# SOS-Water-Ingress-Sensor.net
KiCad netlist of a schematic drawn in EAGLE
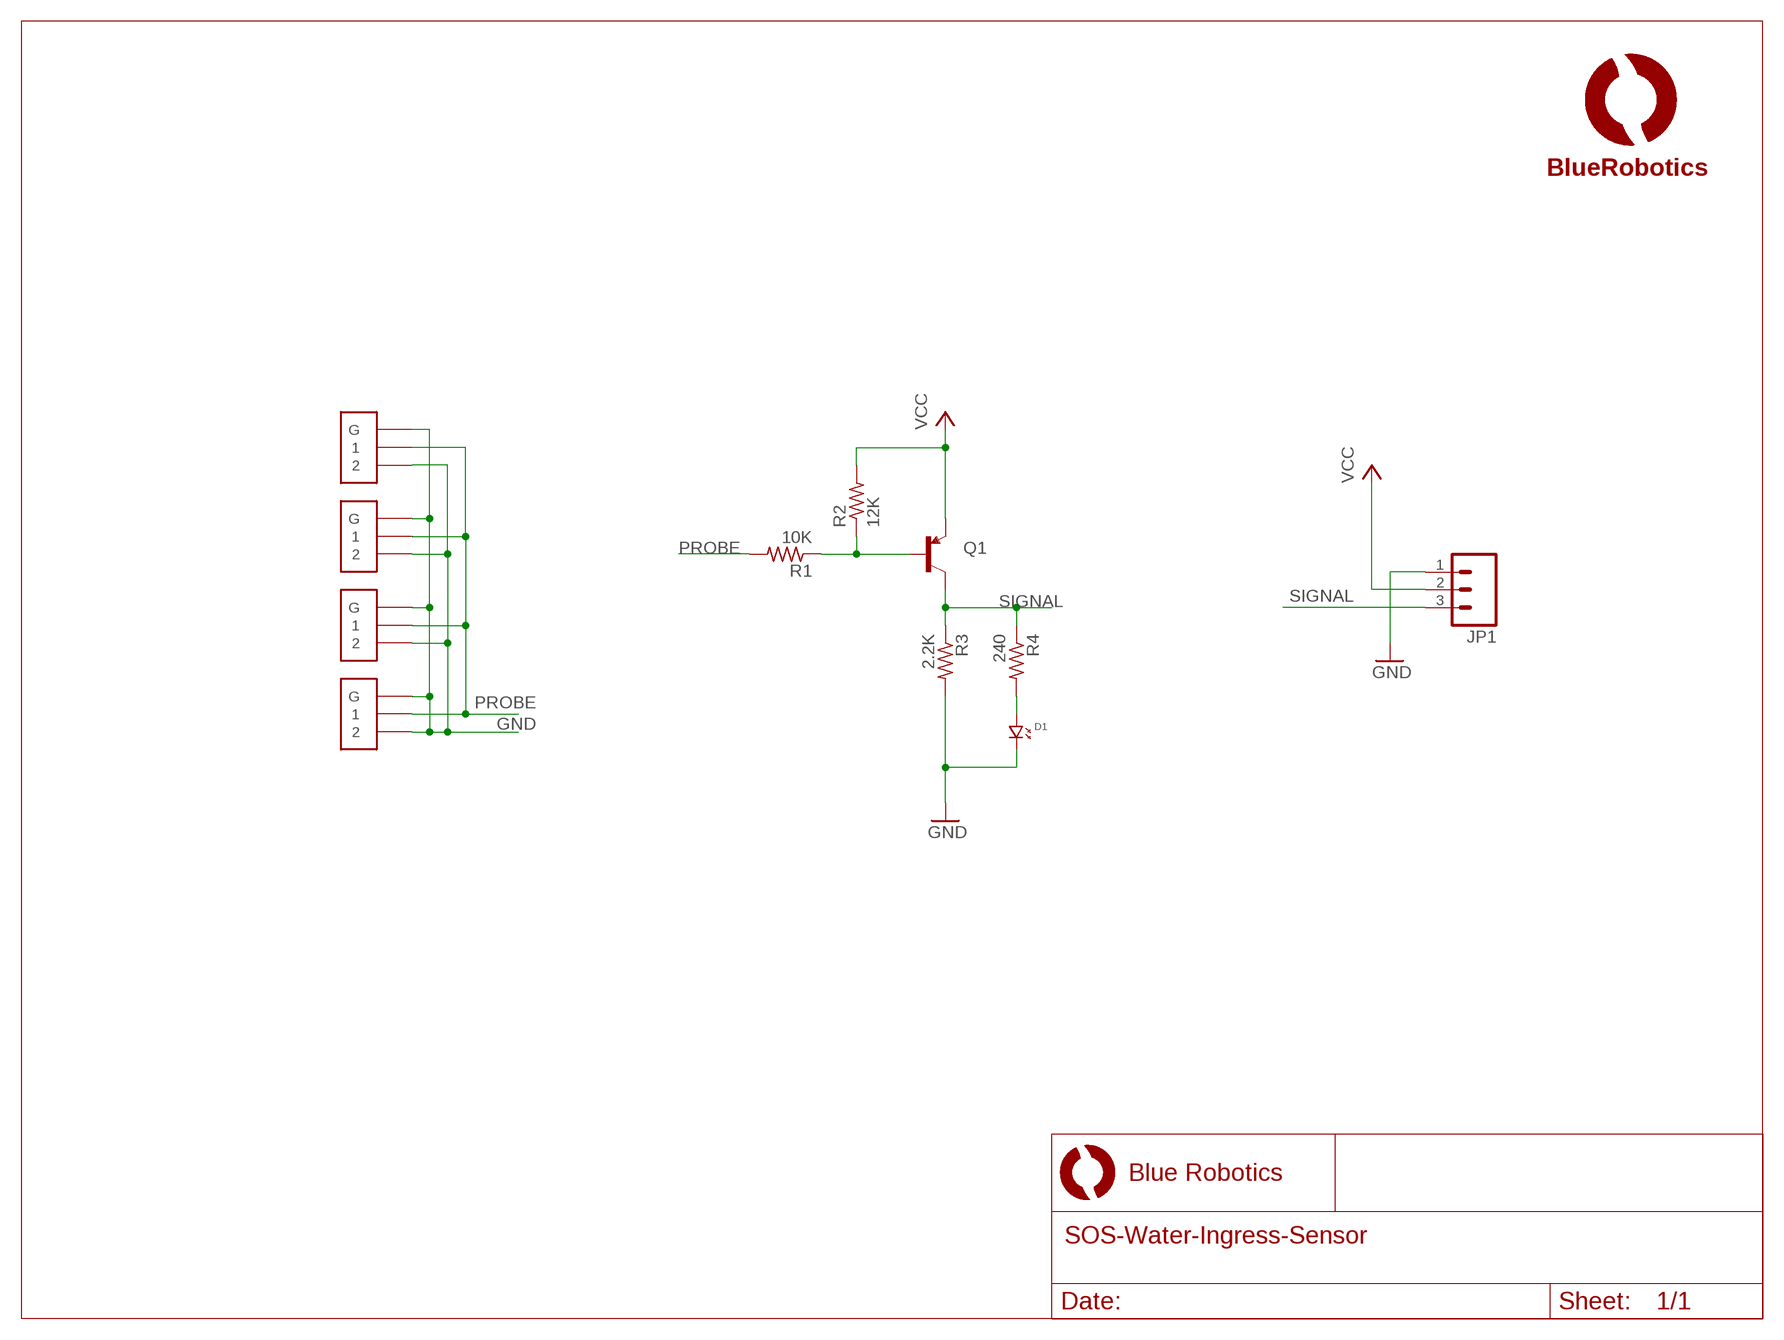
[diagram p0: schematic, sheet 1]

(export (version "E")
  (design (tool "Eeschema 10.0.6"))
  (components
    (comp (ref "D1")
      (value "LED.0805")
      (footprint "eagle-import:0805.LED")
      (libsource (lib "eagle-import") (part "LED.0805"))
    )
    (comp (ref "JP1")
      (value "M03PTH")
      (footprint "eagle-import:1X03")
      (libsource (lib "eagle-import") (part "M03PTH"))
    )
    (comp (ref "Q1")
      (value "TRANSISTOR_PNPSMD")
      (footprint "eagle-import:SOT23-3")
      (libsource (lib "eagle-import") (part "TRANSISTOR_PNPSMD"))
    )
    (comp (ref "R1")
      (value "10K")
      (footprint "eagle-import:R0603")
      (libsource (lib "eagle-import") (part "R-US_R0603"))
    )
    (comp (ref "R2")
      (value "12K")
      (footprint "eagle-import:R0603")
      (libsource (lib "eagle-import") (part "R-US_R0603"))
    )
    (comp (ref "R3")
      (value "2.2K")
      (footprint "eagle-import:R0603")
      (libsource (lib "eagle-import") (part "R-US_R0603"))
    )
    (comp (ref "R4")
      (value "240")
      (footprint "eagle-import:R0603")
      (libsource (lib "eagle-import") (part "R-US_R0603"))
    )
    (comp (ref "U$1")
      (value "JSH-GH-2VERT")
      (footprint "eagle-import:JST-GH-TOP-2")
      (libsource (lib "eagle-import") (part "JSH-GH-2VERT"))
    )
    (comp (ref "U$2")
      (value "JSH-GH-2VERT")
      (footprint "eagle-import:JST-GH-TOP-2")
      (libsource (lib "eagle-import") (part "JSH-GH-2VERT"))
    )
    (comp (ref "U$3")
      (value "JSH-GH-2VERT")
      (footprint "eagle-import:JST-GH-TOP-2")
      (libsource (lib "eagle-import") (part "JSH-GH-2VERT"))
    )
    (comp (ref "U$4")
      (value "JSH-GH-2VERT")
      (footprint "eagle-import:JST-GH-TOP-2")
      (libsource (lib "eagle-import") (part "JSH-GH-2VERT"))
    )
    (comp (ref "U$7")
      (value "LOGOBR-LOGO-S")
      (footprint "eagle-import:BR-LOGO-SMALL")
      (libsource (lib "eagle-import") (part "LOGOBR-LOGO-S"))
    )
  )
  (nets
    (net (code "1") (name "/PROBE") (class "Default")
      (node (ref "R1") (pin "2") (pinfunction "2_2") (pintype "passive"))
      (node (ref "U$1") (pin "1") (pinfunction "1_1") (pintype "bidirectional"))
      (node (ref "U$2") (pin "1") (pinfunction "1_1") (pintype "bidirectional"))
      (node (ref "U$3") (pin "1") (pinfunction "1_1") (pintype "bidirectional"))
      (node (ref "U$4") (pin "1") (pinfunction "1_1") (pintype "bidirectional"))
    )
    (net (code "2") (name "/SIGNAL") (class "Default")
      (node (ref "JP1") (pin "3") (pinfunction "3_3") (pintype "passive"))
      (node (ref "Q1") (pin "3") (pinfunction "C_3") (pintype "passive"))
      (node (ref "R3") (pin "1") (pinfunction "1_1") (pintype "passive"))
      (node (ref "R4") (pin "1") (pinfunction "1_1") (pintype "passive"))
    )
    (net (code "3") (name "GND") (class "Default")
      (node (ref "D1") (pin "P$2") (pinfunction "2_P$2") (pintype "bidirectional"))
      (node (ref "JP1") (pin "1") (pinfunction "1_1") (pintype "passive"))
      (node (ref "R3") (pin "2") (pinfunction "2_2") (pintype "passive"))
      (node (ref "U$1") (pin "2") (pinfunction "2_2") (pintype "bidirectional"))
      (node (ref "U$1") (pin "MECH1") (pinfunction "G_MECH1") (pintype "bidirectional"))
      (node (ref "U$1") (pin "MECH2") (pinfunction "G_MECH2") (pintype "bidirectional"))
      (node (ref "U$2") (pin "2") (pinfunction "2_2") (pintype "bidirectional"))
      (node (ref "U$2") (pin "MECH1") (pinfunction "G_MECH1") (pintype "bidirectional"))
      (node (ref "U$2") (pin "MECH2") (pinfunction "G_MECH2") (pintype "bidirectional"))
      (node (ref "U$3") (pin "2") (pinfunction "2_2") (pintype "bidirectional"))
      (node (ref "U$3") (pin "MECH1") (pinfunction "G_MECH1") (pintype "bidirectional"))
      (node (ref "U$3") (pin "MECH2") (pinfunction "G_MECH2") (pintype "bidirectional"))
      (node (ref "U$4") (pin "2") (pinfunction "2_2") (pintype "bidirectional"))
      (node (ref "U$4") (pin "MECH1") (pinfunction "G_MECH1") (pintype "bidirectional"))
      (node (ref "U$4") (pin "MECH2") (pinfunction "G_MECH2") (pintype "bidirectional"))
    )
    (net (code "4") (name "Net-(D1-1)") (class "Default")
      (node (ref "D1") (pin "P$1") (pinfunction "1_P$1") (pintype "bidirectional"))
      (node (ref "R4") (pin "2") (pinfunction "2_2") (pintype "passive"))
    )
    (net (code "5") (name "Net-(Q1-B)") (class "Default")
      (node (ref "Q1") (pin "1") (pinfunction "B_1") (pintype "passive"))
      (node (ref "R1") (pin "1") (pinfunction "1_1") (pintype "passive"))
      (node (ref "R2") (pin "1") (pinfunction "1_1") (pintype "passive"))
    )
    (net (code "6") (name "VCC") (class "Default")
      (node (ref "JP1") (pin "2") (pinfunction "2_2") (pintype "passive"))
      (node (ref "Q1") (pin "2") (pinfunction "E_2") (pintype "passive"))
      (node (ref "R2") (pin "2") (pinfunction "2_2") (pintype "passive"))
    )
  )
)
